# ST-LinkV2.net
KiCad netlist of a schematic drawn in Altium Designer
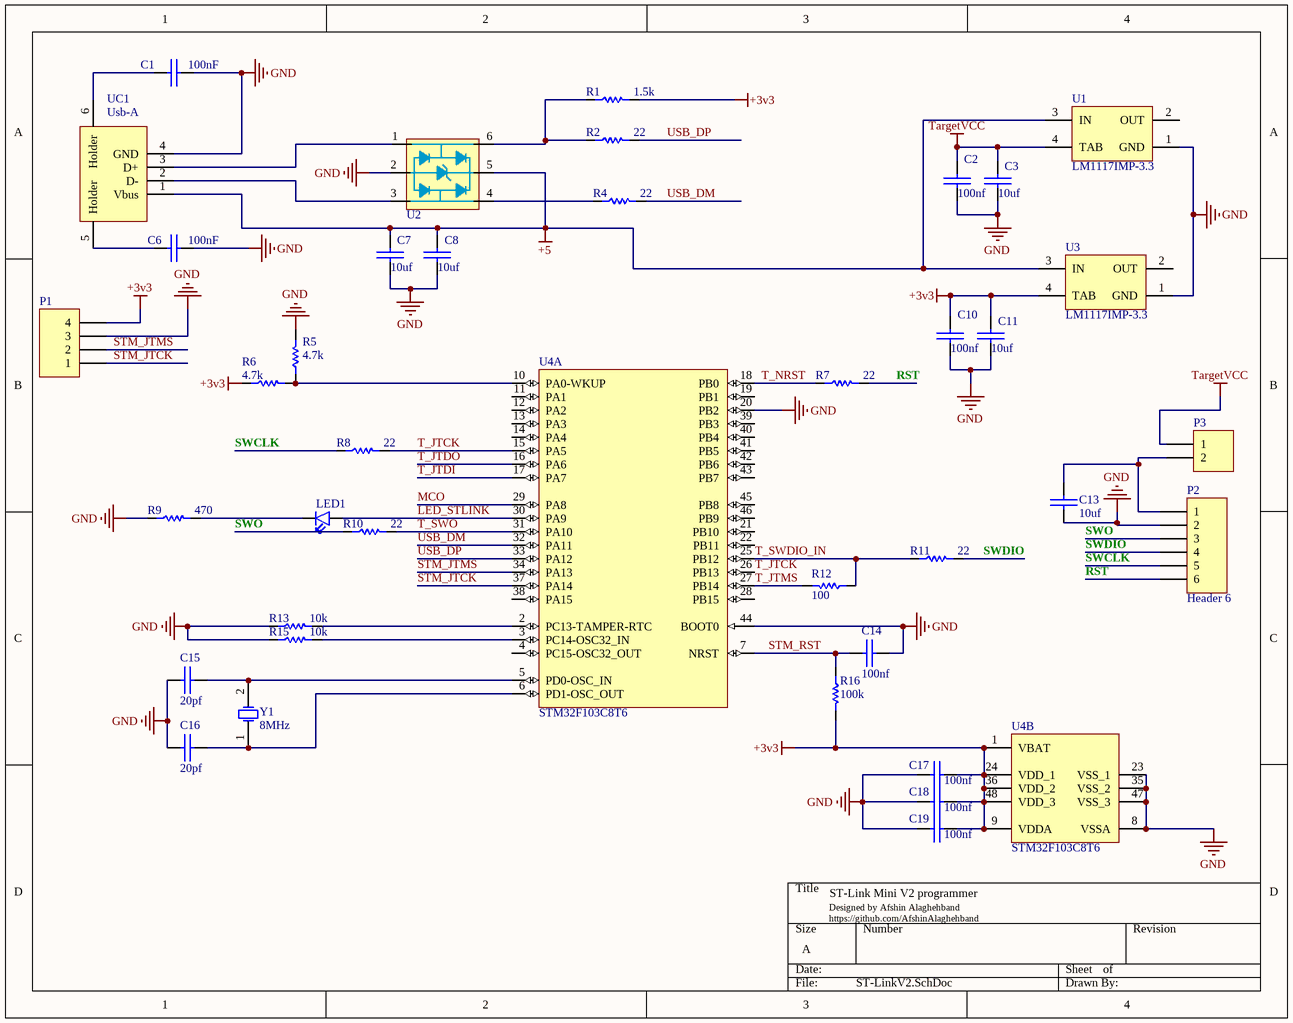
[diagram p0: ST-LinkV2.SchDoc]

(export (version "E")
  (design (tool "Eeschema 10.0.6"))
  (components
    (comp (ref "C1")
      (value "100nF")
      (footprint "SMD_CAP_0805")
      (description "Bipolar Capacitor")
      (fields (field (name "VOLTAGE") "100V") (field (name "DESIGNER") "Saeid Jorablo"))
      (libsource (lib "My Library") (part "Cap-Bipolar"))
    )
    (comp (ref "C2")
      (value "100nf")
      (footprint "SMD_CAP_0805")
      (description "Bipolar Capacitor")
      (fields (field (name "VOLTAGE") "100V") (field (name "DESIGNER") "Saeid Jorablo"))
      (libsource (lib "My Library") (part "Cap-Bipolar"))
    )
    (comp (ref "C3")
      (value "10uf")
      (footprint "SMD_CAP_0805")
      (description "Bipolar Capacitor")
      (fields (field (name "VOLTAGE") "100V") (field (name "DESIGNER") "Saeid Jorablo"))
      (libsource (lib "My Library") (part "Cap-Bipolar"))
    )
    (comp (ref "C6")
      (value "100nF")
      (footprint "SMD_CAP_0805")
      (description "Bipolar Capacitor")
      (fields (field (name "VOLTAGE") "100V") (field (name "DESIGNER") "Saeid Jorablo"))
      (libsource (lib "My Library") (part "Cap-Bipolar"))
    )
    (comp (ref "C7")
      (value "10uf")
      (footprint "SMD_CAP_0805")
      (description "Bipolar Capacitor")
      (fields (field (name "VOLTAGE") "100V") (field (name "DESIGNER") "Saeid Jorablo"))
      (libsource (lib "My Library") (part "Cap-Bipolar"))
    )
    (comp (ref "C8")
      (value "10uf")
      (footprint "SMD_CAP_0805")
      (description "Bipolar Capacitor")
      (fields (field (name "VOLTAGE") "100V") (field (name "DESIGNER") "Saeid Jorablo"))
      (libsource (lib "My Library") (part "Cap-Bipolar"))
    )
    (comp (ref "C10")
      (value "100nf")
      (footprint "SMD_CAP_0805")
      (description "Bipolar Capacitor")
      (fields (field (name "VOLTAGE") "100V") (field (name "DESIGNER") "Saeid Jorablo"))
      (libsource (lib "My Library") (part "Cap-Bipolar"))
    )
    (comp (ref "C11")
      (value "10uf")
      (footprint "SMD_CAP_0805")
      (description "Bipolar Capacitor")
      (fields (field (name "VOLTAGE") "100V") (field (name "DESIGNER") "Saeid Jorablo"))
      (libsource (lib "My Library") (part "Cap-Bipolar"))
    )
    (comp (ref "C13")
      (value "10uf")
      (footprint "SMD_CAP_0805")
      (description "Bipolar Capacitor")
      (fields (field (name "VOLTAGE") "100V") (field (name "DESIGNER") "Saeid Jorablo"))
      (libsource (lib "My Library") (part "Cap-Bipolar"))
    )
    (comp (ref "C14")
      (value "100nf")
      (footprint "SMD_CAP_0805")
      (description "Bipolar Capacitor")
      (fields (field (name "VOLTAGE") "100V") (field (name "DESIGNER") "Saeid Jorablo"))
      (libsource (lib "My Library") (part "Cap-Bipolar"))
    )
    (comp (ref "C15")
      (value "20pf")
      (footprint "SMD_CAP_0805")
      (description "Bipolar Capacitor")
      (fields (field (name "VOLTAGE") "100V") (field (name "DESIGNER") "Saeid Jorablo"))
      (libsource (lib "My Library") (part "Cap-Bipolar"))
    )
    (comp (ref "C16")
      (value "20pf")
      (footprint "SMD_CAP_0805")
      (description "Bipolar Capacitor")
      (fields (field (name "VOLTAGE") "100V") (field (name "DESIGNER") "Saeid Jorablo"))
      (libsource (lib "My Library") (part "Cap-Bipolar"))
    )
    (comp (ref "C17")
      (value "100nf")
      (footprint "SMD_CAP_0805")
      (description "Bipolar Capacitor")
      (fields (field (name "VOLTAGE") "100V") (field (name "DESIGNER") "Saeid Jorablo"))
      (libsource (lib "My Library") (part "Cap-Bipolar"))
    )
    (comp (ref "C18")
      (value "100nf")
      (footprint "SMD_CAP_0805")
      (description "Bipolar Capacitor")
      (fields (field (name "VOLTAGE") "100V") (field (name "DESIGNER") "Saeid Jorablo"))
      (libsource (lib "My Library") (part "Cap-Bipolar"))
    )
    (comp (ref "C19")
      (value "100nf")
      (footprint "SMD_CAP_0805")
      (description "Bipolar Capacitor")
      (fields (field (name "VOLTAGE") "100V") (field (name "DESIGNER") "Saeid Jorablo"))
      (libsource (lib "My Library") (part "Cap-Bipolar"))
    )
    (comp (ref "LED1")
      (value "LED")
      (footprint "LED0805")
      (description "0805")
      (fields (field (name "DESIGNER :") "Razi Research Team Of Mashhad - Hamed Jafarzadeh"))
      (libsource (lib "R2T Team Library") (part "LED"))
    )
    (comp (ref "P1")
      (value "Header 4")
      (footprint "HDR1X4")
      (description "Header, 4-Pin")
      (fields (field (name "PUBLISHER") "Altium Limited"))
      (libsource (lib "Miscellaneous Connectors") (part "Header 4"))
    )
    (comp (ref "P2")
      (value "Header 6")
      (footprint "HDR1X6")
      (description "Header, 6-Pin")
      (fields (field (name "PUBLISHER") "Altium Limited"))
      (libsource (lib "Miscellaneous Connectors") (part "Header 6"))
    )
    (comp (ref "P3")
      (value "Header 2")
      (footprint "HDR1X2")
      (description "Header, 2-Pin")
      (fields (field (name "PUBLISHER") "Altium Limited"))
      (libsource (lib "Miscellaneous Connectors") (part "Header 2"))
    )
    (comp (ref "R1")
      (value "1.5k")
      (footprint "RES 0805 (2012X06L)")
      (description "Resistor")
      (fields (field (name "TOLERANCE") "5%") (field (name "POWER") "1/8 W"))
      (libsource (lib "My Library") (part "Resistor"))
    )
    (comp (ref "R2")
      (value "22")
      (footprint "RES 0805 (2012X06L)")
      (description "Resistor")
      (fields (field (name "TOLERANCE") "5%") (field (name "POWER") "1/8 W"))
      (libsource (lib "My Library") (part "Resistor"))
    )
    (comp (ref "R4")
      (value "22")
      (footprint "RES 0805 (2012X06L)")
      (description "Resistor")
      (fields (field (name "TOLERANCE") "5%") (field (name "POWER") "1/8 W"))
      (libsource (lib "My Library") (part "Resistor"))
    )
    (comp (ref "R5")
      (value "4.7k")
      (footprint "RES 0805 (2012X06L)")
      (description "Resistor")
      (fields (field (name "TOLERANCE") "5%") (field (name "POWER") "1/8 W"))
      (libsource (lib "My Library") (part "Resistor"))
    )
    (comp (ref "R6")
      (value "4.7k")
      (footprint "RES 0805 (2012X06L)")
      (description "Resistor")
      (fields (field (name "TOLERANCE") "5%") (field (name "POWER") "1/8 W"))
      (libsource (lib "My Library") (part "Resistor"))
    )
    (comp (ref "R7")
      (value "22")
      (footprint "RES 0805 (2012X06L)")
      (description "Resistor")
      (fields (field (name "TOLERANCE") "5%") (field (name "POWER") "1/8 W"))
      (libsource (lib "My Library") (part "Resistor"))
    )
    (comp (ref "R8")
      (value "22")
      (footprint "RES 0805 (2012X06L)")
      (description "Resistor")
      (fields (field (name "TOLERANCE") "5%") (field (name "POWER") "1/8 W"))
      (libsource (lib "My Library") (part "Resistor"))
    )
    (comp (ref "R9")
      (value "470")
      (footprint "RES 0805 (2012X06L)")
      (description "Resistor")
      (fields (field (name "TOLERANCE") "5%") (field (name "POWER") "1/8 W"))
      (libsource (lib "My Library") (part "Resistor"))
    )
    (comp (ref "R10")
      (value "22")
      (footprint "RES 0805 (2012X06L)")
      (description "Resistor")
      (fields (field (name "TOLERANCE") "5%") (field (name "POWER") "1/8 W"))
      (libsource (lib "My Library") (part "Resistor"))
    )
    (comp (ref "R11")
      (value "22")
      (footprint "RES 0805 (2012X06L)")
      (description "Resistor")
      (fields (field (name "TOLERANCE") "5%") (field (name "POWER") "1/8 W"))
      (libsource (lib "My Library") (part "Resistor"))
    )
    (comp (ref "R12")
      (value "100")
      (footprint "RES 0805 (2012X06L)")
      (description "Resistor")
      (fields (field (name "TOLERANCE") "5%") (field (name "POWER") "1/8 W"))
      (libsource (lib "My Library") (part "Resistor"))
    )
    (comp (ref "R13")
      (value "10k")
      (footprint "RES 0805 (2012X06L)")
      (description "Resistor")
      (fields (field (name "TOLERANCE") "5%") (field (name "POWER") "1/8 W"))
      (libsource (lib "My Library") (part "Resistor"))
    )
    (comp (ref "R15")
      (value "10k")
      (footprint "RES 0805 (2012X06L)")
      (description "Resistor")
      (fields (field (name "TOLERANCE") "5%") (field (name "POWER") "1/8 W"))
      (libsource (lib "My Library") (part "Resistor"))
    )
    (comp (ref "R16")
      (value "100k")
      (footprint "RES 0805 (2012X06L)")
      (description "Resistor")
      (fields (field (name "TOLERANCE") "5%") (field (name "POWER") "1/8 W"))
      (libsource (lib "My Library") (part "Resistor"))
    )
    (comp (ref "U1")
      (value "LM1117IMP-3.3")
      (footprint "MP04A_N")
      (description "3.3 Volt, 800mA")
      (fields
        (field (name "MANUFACTURER") "National Semiconductor")
        (field (name "PUBLISHER") "Altium Limited")
      )
      (libsource (lib "My Library") (part "LM1117IMP-x.x"))
    )
    (comp (ref "U2")
      (value "USBLC6-2")
      (footprint "USBLC6-2")
      (fields (field (name "DESIGNER") "Hamed Jafarzadeh"))
      (libsource (lib "R2T Team Library") (part "USBLC6-2"))
    )
    (comp (ref "U3")
      (value "LM1117IMP-3.3")
      (footprint "MP04A_N")
      (description "3.3 Volt, 800mA")
      (fields
        (field (name "MANUFACTURER") "National Semiconductor")
        (field (name "PUBLISHER") "Altium Limited")
      )
      (libsource (lib "My Library") (part "LM1117IMP-x.x"))
    )
    (comp (ref "U4")
      (value "STM32F103C8T6")
      (footprint "STM-LQFP48_N")
      (libsource (lib "ST Microelectronics STM32 F1") (part "STM32F103C8T6"))
    )
    (comp (ref "UC1")
      (value "Usb-A")
      (footprint "USB A Connector")
      (fields (field (name "DESIGNER :") "HamedJafarzadeh"))
      (libsource (lib "R2T Team Library") (part "USB"))
    )
    (comp (ref "Y1")
      (value "8MHz")
      (footprint "XTAL Small")
      (description "XTAL Crystal")
      (libsource (lib "My Library") (part "XTAL"))
    )
  )
  (nets
    (net (code "1") (name "+3v3") (class "Default")
      (node (ref "C10") (pin "2") (pinfunction "-_2") (pintype "passive"))
      (node (ref "C11") (pin "2") (pinfunction "-_2") (pintype "passive"))
      (node (ref "C17") (pin "1") (pinfunction "+_1") (pintype "passive"))
      (node (ref "C18") (pin "1") (pinfunction "+_1") (pintype "passive"))
      (node (ref "C19") (pin "1") (pinfunction "+_1") (pintype "passive"))
      (node (ref "P1") (pin "4") (pinfunction "4_4") (pintype "passive"))
      (node (ref "R1") (pin "2") (pinfunction "2_2") (pintype "passive"))
      (node (ref "R16") (pin "2") (pinfunction "2_2") (pintype "passive"))
      (node (ref "R6") (pin "1") (pinfunction "1_1") (pintype "passive"))
      (node (ref "U3") (pin "4") (pinfunction "TAB_4") (pintype "power_in"))
      (node (ref "U4") (pin "1") (pinfunction "VBAT_1") (pintype "power_in"))
      (node (ref "U4") (pin "24") (pinfunction "VDD_1_24") (pintype "power_in"))
      (node (ref "U4") (pin "36") (pinfunction "VDD_2_36") (pintype "power_in"))
      (node (ref "U4") (pin "48") (pinfunction "VDD_3_48") (pintype "power_in"))
      (node (ref "U4") (pin "9") (pinfunction "VDDA_9") (pintype "power_in"))
    )
    (net (code "2") (name "+5") (class "Default")
      (node (ref "C7") (pin "2") (pinfunction "-_2") (pintype "passive"))
      (node (ref "C8") (pin "2") (pinfunction "-_2") (pintype "passive"))
      (node (ref "U1") (pin "3") (pinfunction "IN_3") (pintype "power_in"))
      (node (ref "U2") (pin "5") (pinfunction "0_5") (pintype "passive"))
      (node (ref "U3") (pin "3") (pinfunction "IN_3") (pintype "power_in"))
      (node (ref "UC1") (pin "1") (pinfunction "Vbus_1") (pintype "passive"))
    )
    (net (code "3") (name "/LED_STLINK") (class "Default")
      (node (ref "LED1") (pin "1") (pinfunction "A_1") (pintype "passive"))
      (node (ref "U4") (pin "30") (pinfunction "PA9_30") (pintype "bidirectional"))
    )
    (net (code "4") (name "/MCO") (class "Default")
      (node (ref "U4") (pin "29") (pinfunction "PA8_29") (pintype "bidirectional"))
    )
    (net (code "5") (name "/RST") (class "Default")
      (node (ref "P2") (pin "6") (pinfunction "6_6") (pintype "passive"))
      (node (ref "R7") (pin "2") (pinfunction "2_2") (pintype "passive"))
    )
    (net (code "6") (name "/STM_JTCK") (class "Default")
      (node (ref "P1") (pin "1") (pinfunction "1_1") (pintype "passive"))
      (node (ref "U4") (pin "37") (pinfunction "PA14_37") (pintype "bidirectional"))
    )
    (net (code "7") (name "/STM_JTMS") (class "Default")
      (node (ref "P1") (pin "2") (pinfunction "2_2") (pintype "passive"))
      (node (ref "U4") (pin "34") (pinfunction "PA13_34") (pintype "bidirectional"))
    )
    (net (code "8") (name "/STM_RST") (class "Default")
      (node (ref "C14") (pin "1") (pinfunction "+_1") (pintype "passive"))
      (node (ref "R16") (pin "1") (pinfunction "1_1") (pintype "passive"))
      (node (ref "U4") (pin "7") (pinfunction "NRST_7") (pintype "bidirectional"))
    )
    (net (code "9") (name "/SWCLK") (class "Default")
      (node (ref "P2") (pin "5") (pinfunction "5_5") (pintype "passive"))
      (node (ref "R8") (pin "1") (pinfunction "1_1") (pintype "passive"))
    )
    (net (code "10") (name "/SWDIO") (class "Default")
      (node (ref "P2") (pin "4") (pinfunction "4_4") (pintype "passive"))
      (node (ref "R11") (pin "2") (pinfunction "2_2") (pintype "passive"))
    )
    (net (code "11") (name "/SWO") (class "Default")
      (node (ref "P2") (pin "3") (pinfunction "3_3") (pintype "passive"))
      (node (ref "R10") (pin "1") (pinfunction "1_1") (pintype "passive"))
    )
    (net (code "12") (name "/T_JTCK") (class "Default")
      (node (ref "R8") (pin "2") (pinfunction "2_2") (pintype "passive"))
      (node (ref "U4") (pin "15") (pinfunction "PA5_15") (pintype "bidirectional"))
      (node (ref "U4") (pin "26") (pinfunction "PB13_26") (pintype "bidirectional"))
    )
    (net (code "13") (name "/T_JTDI") (class "Default")
      (node (ref "U4") (pin "17") (pinfunction "PA7_17") (pintype "bidirectional"))
    )
    (net (code "14") (name "/T_JTDO") (class "Default")
      (node (ref "U4") (pin "16") (pinfunction "PA6_16") (pintype "bidirectional"))
    )
    (net (code "15") (name "/T_JTMS") (class "Default")
      (node (ref "R12") (pin "2") (pinfunction "2_2") (pintype "passive"))
      (node (ref "U4") (pin "27") (pinfunction "PB14_27") (pintype "bidirectional"))
    )
    (net (code "16") (name "/T_NRST") (class "Default")
      (node (ref "R7") (pin "1") (pinfunction "1_1") (pintype "passive"))
      (node (ref "U4") (pin "18") (pinfunction "PB0_18") (pintype "bidirectional"))
    )
    (net (code "17") (name "/T_SWDIO_IN") (class "Default")
      (node (ref "R11") (pin "1") (pinfunction "1_1") (pintype "passive"))
      (node (ref "R12") (pin "1") (pinfunction "1_1") (pintype "passive"))
      (node (ref "U4") (pin "25") (pinfunction "PB12_25") (pintype "bidirectional"))
    )
    (net (code "18") (name "/T_SWO") (class "Default")
      (node (ref "R10") (pin "2") (pinfunction "2_2") (pintype "passive"))
      (node (ref "U4") (pin "31") (pinfunction "PA10_31") (pintype "bidirectional"))
    )
    (net (code "19") (name "/USB_DM") (class "Default")
      (node (ref "R4") (pin "2") (pinfunction "2_2") (pintype "passive"))
      (node (ref "U4") (pin "32") (pinfunction "PA11_32") (pintype "bidirectional"))
    )
    (net (code "20") (name "/USB_DP") (class "Default")
      (node (ref "R2") (pin "2") (pinfunction "2_2") (pintype "passive"))
      (node (ref "U4") (pin "33") (pinfunction "PA12_33") (pintype "bidirectional"))
    )
    (net (code "21") (name "GND") (class "Default")
      (node (ref "C1") (pin "2") (pinfunction "-_2") (pintype "passive"))
      (node (ref "C10") (pin "1") (pinfunction "+_1") (pintype "passive"))
      (node (ref "C11") (pin "1") (pinfunction "+_1") (pintype "passive"))
      (node (ref "C13") (pin "1") (pinfunction "+_1") (pintype "passive"))
      (node (ref "C14") (pin "2") (pinfunction "-_2") (pintype "passive"))
      (node (ref "C15") (pin "1") (pinfunction "+_1") (pintype "passive"))
      (node (ref "C16") (pin "1") (pinfunction "+_1") (pintype "passive"))
      (node (ref "C17") (pin "2") (pinfunction "-_2") (pintype "passive"))
      (node (ref "C18") (pin "2") (pinfunction "-_2") (pintype "passive"))
      (node (ref "C19") (pin "2") (pinfunction "-_2") (pintype "passive"))
      (node (ref "C2") (pin "1") (pinfunction "+_1") (pintype "passive"))
      (node (ref "C3") (pin "1") (pinfunction "+_1") (pintype "passive"))
      (node (ref "C6") (pin "2") (pinfunction "-_2") (pintype "passive"))
      (node (ref "C7") (pin "1") (pinfunction "+_1") (pintype "passive"))
      (node (ref "C8") (pin "1") (pinfunction "+_1") (pintype "passive"))
      (node (ref "P1") (pin "3") (pinfunction "3_3") (pintype "passive"))
      (node (ref "P2") (pin "2") (pinfunction "2_2") (pintype "passive"))
      (node (ref "R13") (pin "1") (pinfunction "1_1") (pintype "passive"))
      (node (ref "R15") (pin "1") (pinfunction "1_1") (pintype "passive"))
      (node (ref "R5") (pin "2") (pinfunction "2_2") (pintype "passive"))
      (node (ref "R9") (pin "1") (pinfunction "1_1") (pintype "passive"))
      (node (ref "U1") (pin "1") (pinfunction "GND_1") (pintype "power_in"))
      (node (ref "U2") (pin "2") (pinfunction "0_2") (pintype "passive"))
      (node (ref "U3") (pin "1") (pinfunction "GND_1") (pintype "power_in"))
      (node (ref "U4") (pin "20") (pinfunction "PB2_20") (pintype "bidirectional"))
      (node (ref "U4") (pin "23") (pinfunction "VSS_1_23") (pintype "power_in"))
      (node (ref "U4") (pin "35") (pinfunction "VSS_2_35") (pintype "power_in"))
      (node (ref "U4") (pin "44") (pinfunction "BOOT0_44") (pintype "input"))
      (node (ref "U4") (pin "47") (pinfunction "VSS_3_47") (pintype "power_in"))
      (node (ref "U4") (pin "8") (pinfunction "VSSA_8") (pintype "power_in"))
      (node (ref "UC1") (pin "4") (pinfunction "GND_4") (pintype "passive"))
    )
    (net (code "22") (name "Net-(C1-+)") (class "Default")
      (node (ref "C1") (pin "1") (pinfunction "+_1") (pintype "passive"))
      (node (ref "UC1") (pin "6") (pinfunction "Holder_6") (pintype "passive"))
    )
    (net (code "23") (name "Net-(C6-+)") (class "Default")
      (node (ref "C6") (pin "1") (pinfunction "+_1") (pintype "passive"))
      (node (ref "UC1") (pin "5") (pinfunction "Holder_5") (pintype "passive"))
    )
    (net (code "24") (name "Net-(C13--)") (class "Default")
      (node (ref "C13") (pin "2") (pinfunction "-_2") (pintype "passive"))
      (node (ref "P2") (pin "1") (pinfunction "1_1") (pintype "passive"))
      (node (ref "P3") (pin "2") (pinfunction "2_2") (pintype "passive"))
    )
    (net (code "25") (name "Net-(C15--)") (class "Default")
      (node (ref "C15") (pin "2") (pinfunction "-_2") (pintype "passive"))
      (node (ref "U4") (pin "5") (pinfunction "PD0-OSC_IN_5") (pintype "bidirectional"))
      (node (ref "Y1") (pin "2") (pinfunction "OSC2_2") (pintype "passive"))
    )
    (net (code "26") (name "Net-(C16--)") (class "Default")
      (node (ref "C16") (pin "2") (pinfunction "-_2") (pintype "passive"))
      (node (ref "U4") (pin "6") (pinfunction "PD1-OSC_OUT_6") (pintype "bidirectional"))
      (node (ref "Y1") (pin "1") (pinfunction "OSC1_1") (pintype "passive"))
    )
    (net (code "27") (name "Net-(LED1-K)") (class "Default")
      (node (ref "LED1") (pin "2") (pinfunction "K_2") (pintype "passive"))
      (node (ref "R9") (pin "2") (pinfunction "2_2") (pintype "passive"))
    )
    (net (code "28") (name "Net-(R4-Pad1)") (class "Default")
      (node (ref "R4") (pin "1") (pinfunction "1_1") (pintype "passive"))
      (node (ref "U2") (pin "4") (pinfunction "0_4") (pintype "passive"))
    )
    (net (code "29") (name "Net-(U2-IO)") (class "Default")
      (node (ref "R1") (pin "1") (pinfunction "1_1") (pintype "passive"))
      (node (ref "R2") (pin "1") (pinfunction "1_1") (pintype "passive"))
      (node (ref "U2") (pin "6") (pinfunction "IO_6") (pintype "passive"))
    )
    (net (code "30") (name "Net-(U4A-PA0-WKUP)") (class "Default")
      (node (ref "R5") (pin "1") (pinfunction "1_1") (pintype "passive"))
      (node (ref "R6") (pin "2") (pinfunction "2_2") (pintype "passive"))
      (node (ref "U4") (pin "10") (pinfunction "PA0-WKUP_10") (pintype "bidirectional"))
    )
    (net (code "31") (name "Net-(U4A-PC13-TAMPER-RTC)") (class "Default")
      (node (ref "R13") (pin "2") (pinfunction "2_2") (pintype "passive"))
      (node (ref "U4") (pin "2") (pinfunction "PC13-TAMPER-RTC_2") (pintype "bidirectional"))
    )
    (net (code "32") (name "Net-(U4A-PC14-OSC32_IN)") (class "Default")
      (node (ref "R15") (pin "2") (pinfunction "2_2") (pintype "passive"))
      (node (ref "U4") (pin "3") (pinfunction "PC14-OSC32_IN_3") (pintype "bidirectional"))
    )
    (net (code "33") (name "Net-(UC1-D+)") (class "Default")
      (node (ref "U2") (pin "1") (pinfunction "0_1") (pintype "passive"))
      (node (ref "UC1") (pin "3") (pinfunction "D+_3") (pintype "passive"))
    )
    (net (code "34") (name "Net-(UC1-D-)") (class "Default")
      (node (ref "U2") (pin "3") (pinfunction "0_3") (pintype "passive"))
      (node (ref "UC1") (pin "2") (pinfunction "D-_2") (pintype "passive"))
    )
    (net (code "35") (name "TargetVCC") (class "Default")
      (node (ref "C2") (pin "2") (pinfunction "-_2") (pintype "passive"))
      (node (ref "C3") (pin "2") (pinfunction "-_2") (pintype "passive"))
      (node (ref "P3") (pin "1") (pinfunction "1_1") (pintype "passive"))
      (node (ref "U1") (pin "4") (pinfunction "TAB_4") (pintype "power_in"))
    )
    (net (code "36") (name "unconnected-(U1-OUT-Pad2)") (class "Default")
      (node (ref "U1") (pin "2") (pinfunction "OUT_2") (pintype "power_in"))
    )
    (net (code "37") (name "unconnected-(U3-OUT-Pad2)") (class "Default")
      (node (ref "U3") (pin "2") (pinfunction "OUT_2") (pintype "power_in"))
    )
    (net (code "38") (name "unconnected-(U4A-PA1-Pad11)") (class "Default")
      (node (ref "U4") (pin "11") (pinfunction "PA1_11") (pintype "bidirectional"))
    )
    (net (code "39") (name "unconnected-(U4A-PA2-Pad12)") (class "Default")
      (node (ref "U4") (pin "12") (pinfunction "PA2_12") (pintype "bidirectional"))
    )
    (net (code "40") (name "unconnected-(U4A-PA3-Pad13)") (class "Default")
      (node (ref "U4") (pin "13") (pinfunction "PA3_13") (pintype "bidirectional"))
    )
    (net (code "41") (name "unconnected-(U4A-PA4-Pad14)") (class "Default")
      (node (ref "U4") (pin "14") (pinfunction "PA4_14") (pintype "bidirectional"))
    )
    (net (code "42") (name "unconnected-(U4A-PA15-Pad38)") (class "Default")
      (node (ref "U4") (pin "38") (pinfunction "PA15_38") (pintype "bidirectional"))
    )
    (net (code "43") (name "unconnected-(U4A-PB1-Pad19)") (class "Default")
      (node (ref "U4") (pin "19") (pinfunction "PB1_19") (pintype "bidirectional"))
    )
    (net (code "44") (name "unconnected-(U4A-PB3-Pad39)") (class "Default")
      (node (ref "U4") (pin "39") (pinfunction "PB3_39") (pintype "bidirectional"))
    )
    (net (code "45") (name "unconnected-(U4A-PB4-Pad40)") (class "Default")
      (node (ref "U4") (pin "40") (pinfunction "PB4_40") (pintype "bidirectional"))
    )
    (net (code "46") (name "unconnected-(U4A-PB5-Pad41)") (class "Default")
      (node (ref "U4") (pin "41") (pinfunction "PB5_41") (pintype "bidirectional"))
    )
    (net (code "47") (name "unconnected-(U4A-PB6-Pad42)") (class "Default")
      (node (ref "U4") (pin "42") (pinfunction "PB6_42") (pintype "bidirectional"))
    )
    (net (code "48") (name "unconnected-(U4A-PB7-Pad43)") (class "Default")
      (node (ref "U4") (pin "43") (pinfunction "PB7_43") (pintype "bidirectional"))
    )
    (net (code "49") (name "unconnected-(U4A-PB8-Pad45)") (class "Default")
      (node (ref "U4") (pin "45") (pinfunction "PB8_45") (pintype "bidirectional"))
    )
    (net (code "50") (name "unconnected-(U4A-PB9-Pad46)") (class "Default")
      (node (ref "U4") (pin "46") (pinfunction "PB9_46") (pintype "bidirectional"))
    )
    (net (code "51") (name "unconnected-(U4A-PB10-Pad21)") (class "Default")
      (node (ref "U4") (pin "21") (pinfunction "PB10_21") (pintype "bidirectional"))
    )
    (net (code "52") (name "unconnected-(U4A-PB11-Pad22)") (class "Default")
      (node (ref "U4") (pin "22") (pinfunction "PB11_22") (pintype "bidirectional"))
    )
    (net (code "53") (name "unconnected-(U4A-PB15-Pad28)") (class "Default")
      (node (ref "U4") (pin "28") (pinfunction "PB15_28") (pintype "bidirectional"))
    )
    (net (code "54") (name "unconnected-(U4A-PC15-OSC32_OUT-Pad4)") (class "Default")
      (node (ref "U4") (pin "4") (pinfunction "PC15-OSC32_OUT_4") (pintype "bidirectional"))
    )
  )
)
